# Microphone.net
KiCad netlist of a schematic drawn in EAGLE
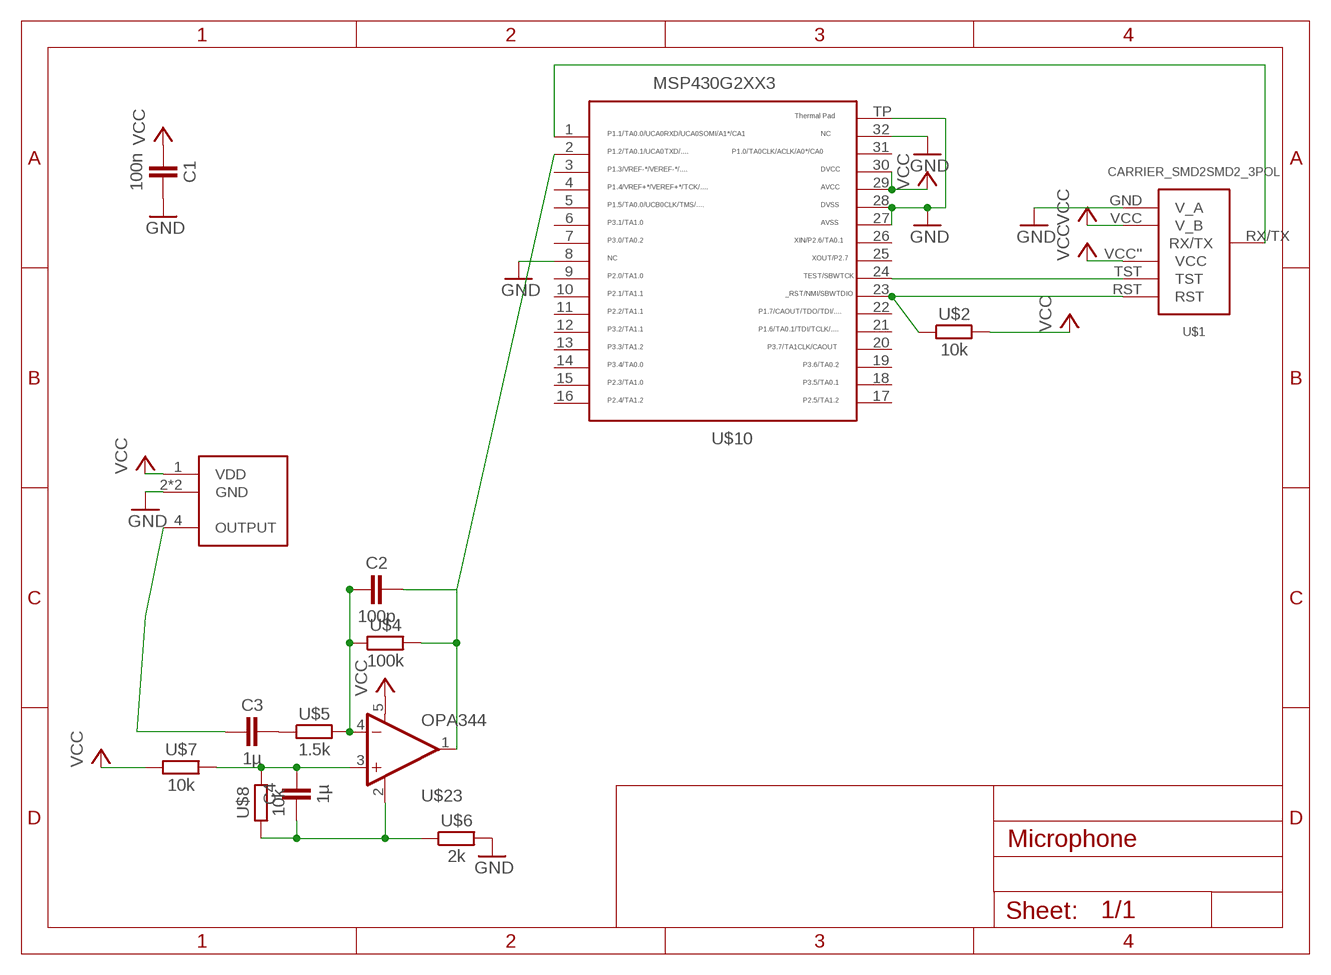
[diagram p0: schematic, sheet 1]

(export (version "E")
  (design (tool "Eeschema 10.0.6"))
  (components
    (comp (ref "C1")
      (value "100n")
      (footprint "eagle-import:603")
      (libsource (lib "eagle-import") (part "CAPACITOR"))
    )
    (comp (ref "C2")
      (value "100p")
      (footprint "eagle-import:603")
      (libsource (lib "eagle-import") (part "CAPACITOR"))
    )
    (comp (ref "C3")
      (value "1µ")
      (footprint "eagle-import:603")
      (libsource (lib "eagle-import") (part "CAPACITOR"))
    )
    (comp (ref "C4")
      (value "1µ")
      (footprint "eagle-import:603")
      (libsource (lib "eagle-import") (part "CAPACITOR"))
    )
    (comp (ref "U$1")
      (value "CARRIER_SMD2SMD2_3POL")
      (footprint "eagle-import:CARRIER_SMD2_3POL")
      (libsource (lib "eagle-import") (part "CARRIER_SMD2SMD2_3POL"))
    )
    (comp (ref "U$2")
      (value "10k")
      (footprint "eagle-import:603")
      (libsource (lib "eagle-import") (part "RESISTOR0603"))
    )
    (comp (ref "U$4")
      (value "100k")
      (footprint "eagle-import:603")
      (libsource (lib "eagle-import") (part "RESISTOR0603"))
    )
    (comp (ref "U$5")
      (value "1.5k")
      (footprint "eagle-import:603")
      (libsource (lib "eagle-import") (part "RESISTOR0603"))
    )
    (comp (ref "U$6")
      (value "2k")
      (footprint "eagle-import:603")
      (libsource (lib "eagle-import") (part "RESISTOR0603"))
    )
    (comp (ref "U$7")
      (value "10k")
      (footprint "eagle-import:603")
      (libsource (lib "eagle-import") (part "RESISTOR0603"))
    )
    (comp (ref "U$8")
      (value "10k")
      (footprint "eagle-import:603")
      (libsource (lib "eagle-import") (part "RESISTOR0603"))
    )
    (comp (ref "U$10")
      (value "MSP430G2553")
      (footprint "eagle-import:QFN32")
      (libsource (lib "eagle-import") (part "MSP430G2553"))
    )
    (comp (ref "U$23")
      (value "OPA344")
      (footprint "eagle-import:SOT23-5")
      (libsource (lib "eagle-import") (part "OPA344"))
    )
    (comp (ref "U$25")
      (value "WM7120A")
      (footprint "eagle-import:WM7120A")
      (libsource (lib "eagle-import") (part "WM7120A"))
    )
  )
  (nets
    (net (code "1") (name "GND") (class "Default")
      (node (ref "C1") (pin "2") (pinfunction "2_2") (pintype "passive"))
      (node (ref "U$1") (pin "GND") (pinfunction "V_A_GND") (pintype "bidirectional"))
      (node (ref "U$10") (pin "27") (pinfunction "27_27") (pintype "bidirectional"))
      (node (ref "U$10") (pin "28") (pinfunction "28_28") (pintype "bidirectional"))
      (node (ref "U$10") (pin "32") (pinfunction "32_32") (pintype "bidirectional"))
      (node (ref "U$10") (pin "8") (pinfunction "8_8") (pintype "bidirectional"))
      (node (ref "U$10") (pin "TP") (pinfunction "TP_TP") (pintype "bidirectional"))
      (node (ref "U$25") (pin "2") (pinfunction "GND_2") (pintype "output"))
      (node (ref "U$25") (pin "3") (pinfunction "GND_3") (pintype "output"))
      (node (ref "U$6") (pin "2") (pinfunction "2_2") (pintype "passive"))
    )
    (net (code "2") (name "Net-(C3-Pad2)") (class "Default")
      (node (ref "C3") (pin "2") (pinfunction "2_2") (pintype "passive"))
      (node (ref "U$5") (pin "1") (pinfunction "1_1") (pintype "passive"))
    )
    (net (code "3") (name "Net-(U$1-PadRST)") (class "Default")
      (node (ref "U$1") (pin "RST") (pinfunction "RST_RST") (pintype "bidirectional"))
      (node (ref "U$10") (pin "23") (pinfunction "23_23") (pintype "bidirectional"))
      (node (ref "U$2") (pin "1") (pinfunction "1_1") (pintype "passive"))
    )
    (net (code "4") (name "Net-(U$1-PadRX{slash}TX)") (class "Default")
      (node (ref "U$1") (pin "RX/TX") (pinfunction "RX/TX_RX/TX") (pintype "bidirectional"))
      (node (ref "U$10") (pin "1") (pinfunction "1_1") (pintype "bidirectional"))
    )
    (net (code "5") (name "Net-(U$1-PadTST)") (class "Default")
      (node (ref "U$1") (pin "TST") (pinfunction "TST_TST") (pintype "bidirectional"))
      (node (ref "U$10") (pin "24") (pinfunction "24_24") (pintype "bidirectional"))
    )
    (net (code "6") (name "Net-(U$23-+IN)") (class "Default")
      (node (ref "C4") (pin "2") (pinfunction "2_2") (pintype "passive"))
      (node (ref "U$23") (pin "3") (pinfunction "+IN_3") (pintype "input"))
      (node (ref "U$7") (pin "2") (pinfunction "2_2") (pintype "passive"))
      (node (ref "U$8") (pin "2") (pinfunction "2_2") (pintype "passive"))
    )
    (net (code "7") (name "Net-(U$23--IN)") (class "Default")
      (node (ref "C2") (pin "1") (pinfunction "1_1") (pintype "passive"))
      (node (ref "U$23") (pin "4") (pinfunction "-IN_4") (pintype "input"))
      (node (ref "U$4") (pin "1") (pinfunction "1_1") (pintype "passive"))
      (node (ref "U$5") (pin "2") (pinfunction "2_2") (pintype "passive"))
    )
    (net (code "8") (name "Net-(U$23-OUT)") (class "Default")
      (node (ref "C2") (pin "2") (pinfunction "2_2") (pintype "passive"))
      (node (ref "U$10") (pin "2") (pinfunction "2_2") (pintype "bidirectional"))
      (node (ref "U$23") (pin "1") (pinfunction "OUT_1") (pintype "output"))
      (node (ref "U$4") (pin "2") (pinfunction "2_2") (pintype "passive"))
    )
    (net (code "9") (name "Net-(U$23-V-)") (class "Default")
      (node (ref "C4") (pin "1") (pinfunction "1_1") (pintype "passive"))
      (node (ref "U$23") (pin "2") (pinfunction "V-_2") (pintype "power_in"))
      (node (ref "U$6") (pin "1") (pinfunction "1_1") (pintype "passive"))
      (node (ref "U$8") (pin "1") (pinfunction "1_1") (pintype "passive"))
    )
    (net (code "10") (name "Net-(U$25-OUTPUT)") (class "Default")
      (node (ref "C3") (pin "1") (pinfunction "1_1") (pintype "passive"))
      (node (ref "U$25") (pin "4") (pinfunction "OUTPUT_4") (pintype "output"))
    )
    (net (code "11") (name "VCC") (class "Default")
      (node (ref "C1") (pin "1") (pinfunction "1_1") (pintype "passive"))
      (node (ref "U$1") (pin "VCC") (pinfunction "V_B_VCC") (pintype "bidirectional"))
      (node (ref "U$1") (pin "VCC''") (pinfunction "VCC_VCC''") (pintype "bidirectional"))
      (node (ref "U$10") (pin "29") (pinfunction "29_29") (pintype "bidirectional"))
      (node (ref "U$10") (pin "30") (pinfunction "30_30") (pintype "bidirectional"))
      (node (ref "U$2") (pin "2") (pinfunction "2_2") (pintype "passive"))
      (node (ref "U$23") (pin "5") (pinfunction "V+_5") (pintype "power_in"))
      (node (ref "U$25") (pin "1") (pinfunction "VDD_1") (pintype "output"))
      (node (ref "U$7") (pin "1") (pinfunction "1_1") (pintype "passive"))
    )
    (net (code "12") (name "unconnected-(U$10-Pad3)") (class "Default")
      (node (ref "U$10") (pin "3") (pinfunction "3_3") (pintype "bidirectional"))
    )
    (net (code "13") (name "unconnected-(U$10-Pad4)") (class "Default")
      (node (ref "U$10") (pin "4") (pinfunction "4_4") (pintype "bidirectional"))
    )
    (net (code "14") (name "unconnected-(U$10-Pad5)") (class "Default")
      (node (ref "U$10") (pin "5") (pinfunction "5_5") (pintype "bidirectional"))
    )
    (net (code "15") (name "unconnected-(U$10-Pad6)") (class "Default")
      (node (ref "U$10") (pin "6") (pinfunction "6_6") (pintype "bidirectional"))
    )
    (net (code "16") (name "unconnected-(U$10-Pad7)") (class "Default")
      (node (ref "U$10") (pin "7") (pinfunction "7_7") (pintype "bidirectional"))
    )
    (net (code "17") (name "unconnected-(U$10-Pad9)") (class "Default")
      (node (ref "U$10") (pin "9") (pinfunction "9_9") (pintype "bidirectional"))
    )
    (net (code "18") (name "unconnected-(U$10-Pad10)") (class "Default")
      (node (ref "U$10") (pin "10") (pinfunction "10_10") (pintype "bidirectional"))
    )
    (net (code "19") (name "unconnected-(U$10-Pad11)") (class "Default")
      (node (ref "U$10") (pin "11") (pinfunction "11_11") (pintype "bidirectional"))
    )
    (net (code "20") (name "unconnected-(U$10-Pad12)") (class "Default")
      (node (ref "U$10") (pin "12") (pinfunction "12_12") (pintype "bidirectional"))
    )
    (net (code "21") (name "unconnected-(U$10-Pad13)") (class "Default")
      (node (ref "U$10") (pin "13") (pinfunction "13_13") (pintype "bidirectional"))
    )
    (net (code "22") (name "unconnected-(U$10-Pad14)") (class "Default")
      (node (ref "U$10") (pin "14") (pinfunction "14_14") (pintype "bidirectional"))
    )
    (net (code "23") (name "unconnected-(U$10-Pad15)") (class "Default")
      (node (ref "U$10") (pin "15") (pinfunction "15_15") (pintype "bidirectional"))
    )
    (net (code "24") (name "unconnected-(U$10-Pad16)") (class "Default")
      (node (ref "U$10") (pin "16") (pinfunction "16_16") (pintype "bidirectional"))
    )
    (net (code "25") (name "unconnected-(U$10-Pad17)") (class "Default")
      (node (ref "U$10") (pin "17") (pinfunction "17_17") (pintype "bidirectional"))
    )
    (net (code "26") (name "unconnected-(U$10-Pad18)") (class "Default")
      (node (ref "U$10") (pin "18") (pinfunction "18_18") (pintype "bidirectional"))
    )
    (net (code "27") (name "unconnected-(U$10-Pad19)") (class "Default")
      (node (ref "U$10") (pin "19") (pinfunction "19_19") (pintype "bidirectional"))
    )
    (net (code "28") (name "unconnected-(U$10-Pad20)") (class "Default")
      (node (ref "U$10") (pin "20") (pinfunction "20_20") (pintype "bidirectional"))
    )
    (net (code "29") (name "unconnected-(U$10-Pad21)") (class "Default")
      (node (ref "U$10") (pin "21") (pinfunction "21_21") (pintype "bidirectional"))
    )
    (net (code "30") (name "unconnected-(U$10-Pad22)") (class "Default")
      (node (ref "U$10") (pin "22") (pinfunction "22_22") (pintype "bidirectional"))
    )
    (net (code "31") (name "unconnected-(U$10-Pad25)") (class "Default")
      (node (ref "U$10") (pin "25") (pinfunction "25_25") (pintype "bidirectional"))
    )
    (net (code "32") (name "unconnected-(U$10-Pad26)") (class "Default")
      (node (ref "U$10") (pin "26") (pinfunction "26_26") (pintype "bidirectional"))
    )
    (net (code "33") (name "unconnected-(U$10-Pad31)") (class "Default")
      (node (ref "U$10") (pin "31") (pinfunction "31_31") (pintype "bidirectional"))
    )
  )
)
